# powerDist.net
KiCad netlist of a schematic drawn in Altium Designer
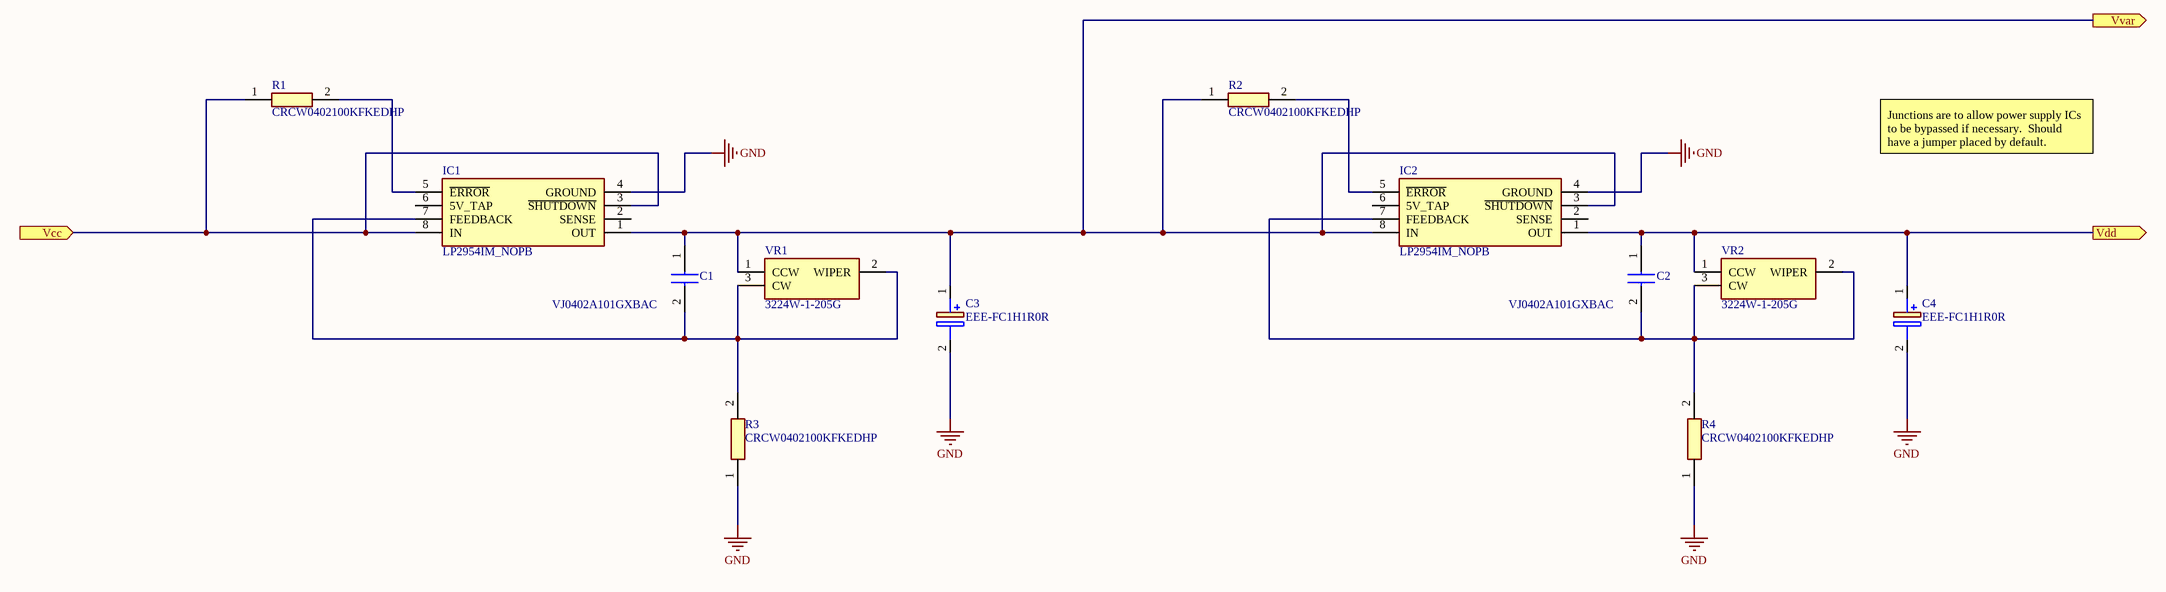
[diagram p0: powerDist.SchDoc]

(export (version "E")
  (design (tool "Eeschema 10.0.6"))
  (components
    (comp (ref "C1")
      (value "VJ0402A101GXBAC")
      (footprint "SamacSys:CAPC1005X55N")
      (description "Capacitor")
      (fields (field (name "MOUSER PART NUMBER") "77-VJ0402A101GXBAC"))
      (libsource (lib "SamacSys") (part "VJ0402A101GXBAC"))
    )
    (comp (ref "C2")
      (value "VJ0402A101GXBAC")
      (footprint "SamacSys:CAPC1005X55N")
      (description "Capacitor")
      (fields (field (name "MOUSER PART NUMBER") "77-VJ0402A101GXBAC"))
      (libsource (lib "SamacSys") (part "VJ0402A101GXBAC"))
    )
    (comp (ref "C3")
      (value "EEE-FC1H1R0R")
      (footprint "SamacSys:EEE1AA220WR")
      (description "Capacitor Polarised")
      (libsource (lib "SamacSys") (part "EEE-FC1H1R0R"))
    )
    (comp (ref "C4")
      (value "EEE-FC1H1R0R")
      (footprint "SamacSys:EEE1AA220WR")
      (description "Capacitor Polarised")
      (libsource (lib "SamacSys") (part "EEE-FC1H1R0R"))
    )
    (comp (ref "IC1")
      (value "LP2954IM_NOPB")
      (footprint "SamacSys:SOIC127P600X175-8N")
      (description "Integrated Circuit")
      (fields
        (field (name "MANUFACTURER_PART_NUMBER") "LP2954IM/NOPB")
        (field (name "MOUSER PART NUMBER") "926-LP2954IM/NOPB")
      )
      (libsource (lib "SamacSys") (part "LP2954IM_NOPB"))
    )
    (comp (ref "IC2")
      (value "LP2954IM_NOPB")
      (footprint "SamacSys:SOIC127P600X175-8N")
      (description "Integrated Circuit")
      (fields
        (field (name "MANUFACTURER_PART_NUMBER") "LP2954IM/NOPB")
        (field (name "MOUSER PART NUMBER") "926-LP2954IM/NOPB")
      )
      (libsource (lib "SamacSys") (part "LP2954IM_NOPB"))
    )
    (comp (ref "R1")
      (value "CRCW0402100KFKEDHP")
      (footprint "SamacSys:RESC1005X40N")
      (description "Resistor")
      (fields (field (name "MOUSER PART NUMBER") "71-CRCW0402100KFKEDH"))
      (libsource (lib "SamacSys") (part "CRCW0402100KFKEDHP"))
    )
    (comp (ref "R2")
      (value "CRCW0402100KFKEDHP")
      (footprint "SamacSys:RESC1005X40N")
      (description "Resistor")
      (fields (field (name "MOUSER PART NUMBER") "71-CRCW0402100KFKEDH"))
      (libsource (lib "SamacSys") (part "CRCW0402100KFKEDHP"))
    )
    (comp (ref "R3")
      (value "CRCW0402100KFKEDHP")
      (footprint "SamacSys:RESC1005X40N")
      (description "Resistor")
      (fields (field (name "MOUSER PART NUMBER") "71-CRCW0402100KFKEDH"))
      (libsource (lib "") (part "CRCW0402100KFKEDHP_1"))
    )
    (comp (ref "R4")
      (value "CRCW0402100KFKEDHP")
      (footprint "SamacSys:RESC1005X40N")
      (description "Resistor")
      (fields (field (name "MOUSER PART NUMBER") "71-CRCW0402100KFKEDH"))
      (libsource (lib "") (part "CRCW0402100KFKEDHP_1"))
    )
    (comp (ref "VR1")
      (value "3224W-1-205G")
      (footprint "SamacSys:3224W1205G")
      (description "Variable Resistor")
      (fields (field (name "MOUSER PART NUMBER") "652-3224W-1-205G"))
      (libsource (lib "SamacSys") (part "3224W-1-205G"))
    )
    (comp (ref "VR2")
      (value "3224W-1-205G")
      (footprint "SamacSys:3224W1205G")
      (description "Variable Resistor")
      (fields (field (name "MOUSER PART NUMBER") "652-3224W-1-205G"))
      (libsource (lib "SamacSys") (part "3224W-1-205G"))
    )
  )
  (nets
    (net (code "1") (name "/Vcc") (class "Default")
      (node (ref "IC1") (pin "3") (pinfunction "~{SHUTDOWN}_3") (pintype "passive"))
      (node (ref "IC1") (pin "8") (pinfunction "IN_8") (pintype "passive"))
      (node (ref "R1") (pin "1") (pinfunction "1_1") (pintype "passive"))
    )
    (net (code "2") (name "/Vdd") (class "Default")
      (node (ref "C2") (pin "1") (pinfunction "1_1") (pintype "passive"))
      (node (ref "C4") (pin "1") (pinfunction "+_1") (pintype "passive"))
      (node (ref "IC2") (pin "1") (pinfunction "OUT_1") (pintype "passive"))
      (node (ref "VR2") (pin "1") (pinfunction "CCW_1") (pintype "passive"))
    )
    (net (code "3") (name "/Vvar") (class "Default")
      (node (ref "C1") (pin "1") (pinfunction "1_1") (pintype "passive"))
      (node (ref "C3") (pin "1") (pinfunction "+_1") (pintype "passive"))
      (node (ref "IC1") (pin "1") (pinfunction "OUT_1") (pintype "passive"))
      (node (ref "IC2") (pin "3") (pinfunction "~{SHUTDOWN}_3") (pintype "passive"))
      (node (ref "IC2") (pin "8") (pinfunction "IN_8") (pintype "passive"))
      (node (ref "R2") (pin "1") (pinfunction "1_1") (pintype "passive"))
      (node (ref "VR1") (pin "1") (pinfunction "CCW_1") (pintype "passive"))
    )
    (net (code "4") (name "GND") (class "Default")
      (node (ref "C3") (pin "2") (pinfunction "-_2") (pintype "passive"))
      (node (ref "C4") (pin "2") (pinfunction "-_2") (pintype "passive"))
      (node (ref "IC1") (pin "4") (pinfunction "GROUND_4") (pintype "passive"))
      (node (ref "IC2") (pin "4") (pinfunction "GROUND_4") (pintype "passive"))
      (node (ref "R3") (pin "1") (pinfunction "1_1") (pintype "passive"))
      (node (ref "R4") (pin "1") (pinfunction "1_1") (pintype "passive"))
    )
    (net (code "5") (name "Net-(IC1-FEEDBACK)") (class "Default")
      (node (ref "C1") (pin "2") (pinfunction "2_2") (pintype "passive"))
      (node (ref "IC1") (pin "7") (pinfunction "FEEDBACK_7") (pintype "passive"))
      (node (ref "R3") (pin "2") (pinfunction "2_2") (pintype "passive"))
      (node (ref "VR1") (pin "2") (pinfunction "WIPER_2") (pintype "passive"))
      (node (ref "VR1") (pin "3") (pinfunction "CW_3") (pintype "passive"))
    )
    (net (code "6") (name "Net-(IC1-~{ERROR})") (class "Default")
      (node (ref "IC1") (pin "5") (pinfunction "~{ERROR}_5") (pintype "passive"))
      (node (ref "R1") (pin "2") (pinfunction "2_2") (pintype "passive"))
    )
    (net (code "7") (name "Net-(IC2-FEEDBACK)") (class "Default")
      (node (ref "C2") (pin "2") (pinfunction "2_2") (pintype "passive"))
      (node (ref "IC2") (pin "7") (pinfunction "FEEDBACK_7") (pintype "passive"))
      (node (ref "R4") (pin "2") (pinfunction "2_2") (pintype "passive"))
      (node (ref "VR2") (pin "2") (pinfunction "WIPER_2") (pintype "passive"))
      (node (ref "VR2") (pin "3") (pinfunction "CW_3") (pintype "passive"))
    )
    (net (code "8") (name "Net-(IC2-~{ERROR})") (class "Default")
      (node (ref "IC2") (pin "5") (pinfunction "~{ERROR}_5") (pintype "passive"))
      (node (ref "R2") (pin "2") (pinfunction "2_2") (pintype "passive"))
    )
    (net (code "9") (name "unconnected-(IC1-5V_TAP-Pad6)") (class "Default")
      (node (ref "IC1") (pin "6") (pinfunction "5V_TAP_6") (pintype "passive"))
    )
    (net (code "10") (name "unconnected-(IC1-SENSE-Pad2)") (class "Default")
      (node (ref "IC1") (pin "2") (pinfunction "SENSE_2") (pintype "passive"))
    )
    (net (code "11") (name "unconnected-(IC2-5V_TAP-Pad6)") (class "Default")
      (node (ref "IC2") (pin "6") (pinfunction "5V_TAP_6") (pintype "passive"))
    )
    (net (code "12") (name "unconnected-(IC2-SENSE-Pad2)") (class "Default")
      (node (ref "IC2") (pin "2") (pinfunction "SENSE_2") (pintype "passive"))
    )
  )
)
